# MCU.net
KiCad netlist of a schematic drawn in Altium Designer
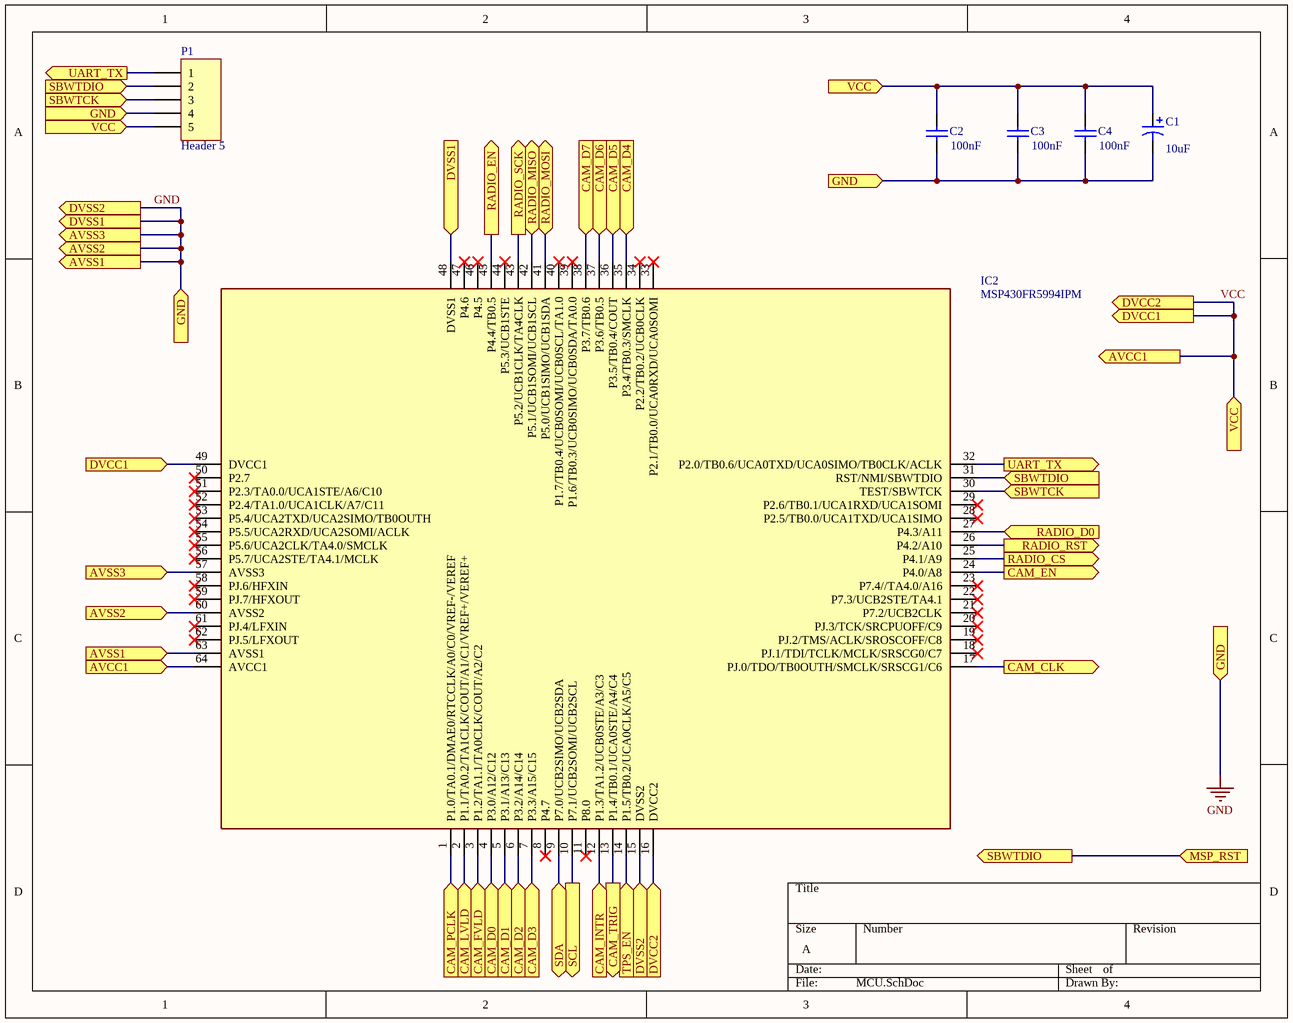
[diagram p0: MCU.SchDoc]

(export (version "E")
  (design (tool "Eeschema 10.0.6"))
  (components
    (comp (ref "C1")
      (value "10uF")
      (footprint "C1210")
      (description "Polarized Capacitor (Surface Mount)")
      (fields (field (name "PUBLISHER") "Altium Limited"))
      (libsource (lib "Miscellaneous Devices") (part "Cap Pol3"))
    )
    (comp (ref "C2")
      (value "100nF")
      (footprint "1608[0603]")
      (description "CAP CER 6.3V X5R/X7R 0603")
      (fields (field (name "Comment") "Cap") (field (name "PUBLISHER") "Altium Limited"))
      (libsource (lib "Miscellaneous Devices") (part "Cap"))
    )
    (comp (ref "C3")
      (value "100nF")
      (footprint "1608[0603]")
      (description "CAP CER 6.3V X5R/X7R 0603")
      (fields (field (name "Comment") "Cap") (field (name "PUBLISHER") "Altium Limited"))
      (libsource (lib "Miscellaneous Devices") (part "Cap"))
    )
    (comp (ref "C4")
      (value "100nF")
      (footprint "1608[0603]")
      (description "CAP CER 6.3V X5R/X7R 0603")
      (fields (field (name "Comment") "Cap") (field (name "PUBLISHER") "Altium Limited"))
      (libsource (lib "Miscellaneous Devices") (part "Cap"))
    )
    (comp (ref "IC2")
      (value "MSP430FR5994IPM")
      (footprint "SamacSys:QFP50P1200X1200X160-64N")
      (description "Integrated Circuit")
      (fields (field (name "MOUSER PART NUMBER") "595-MSP430FR5994IPM"))
      (libsource (lib "*") (part "MSP430FR5994IPM"))
    )
    (comp (ref "P1")
      (value "Header 5")
      (footprint "MHDR1X5")
      (description "Header, 5-Pin")
      (fields (field (name "PUBLISHER") "Altium Limited"))
      (libsource (lib "Miscellaneous Connectors") (part "Header 5"))
    )
  )
  (nets
    (net (code "1") (name "/CAM_CLK") (class "Default")
      (node (ref "IC2") (pin "17") (pinfunction "PJ.0/TDO/TB0OUTH/SMCLK/SRSCG1/C6_17") (pintype "passive"))
    )
    (net (code "2") (name "/CAM_D0") (class "Default")
      (node (ref "IC2") (pin "4") (pinfunction "P3.0/A12/C12_4") (pintype "passive"))
    )
    (net (code "3") (name "/CAM_D1") (class "Default")
      (node (ref "IC2") (pin "5") (pinfunction "P3.1/A13/C13_5") (pintype "passive"))
    )
    (net (code "4") (name "/CAM_D2") (class "Default")
      (node (ref "IC2") (pin "6") (pinfunction "P3.2/A14/C14_6") (pintype "passive"))
    )
    (net (code "5") (name "/CAM_D3") (class "Default")
      (node (ref "IC2") (pin "7") (pinfunction "P3.3/A15/C15_7") (pintype "passive"))
    )
    (net (code "6") (name "/CAM_D4") (class "Default")
      (node (ref "IC2") (pin "35") (pinfunction "P3.4/TB0.3/SMCLK_35") (pintype "passive"))
    )
    (net (code "7") (name "/CAM_D5") (class "Default")
      (node (ref "IC2") (pin "36") (pinfunction "P3.5/TB0.4/COUT_36") (pintype "passive"))
    )
    (net (code "8") (name "/CAM_D6") (class "Default")
      (node (ref "IC2") (pin "37") (pinfunction "P3.6/TB0.5_37") (pintype "passive"))
    )
    (net (code "9") (name "/CAM_D7") (class "Default")
      (node (ref "IC2") (pin "38") (pinfunction "P3.7/TB0.6_38") (pintype "passive"))
    )
    (net (code "10") (name "/CAM_EN") (class "Default")
      (node (ref "IC2") (pin "24") (pinfunction "P4.0/A8_24") (pintype "passive"))
    )
    (net (code "11") (name "/CAM_FVLD") (class "Default")
      (node (ref "IC2") (pin "3") (pinfunction "P1.2/TA1.1/TA0CLK/COUT/A2/C2_3") (pintype "passive"))
    )
    (net (code "12") (name "/CAM_INTR") (class "Default")
      (node (ref "IC2") (pin "12") (pinfunction "P1.3/TA1.2/UCB0STE/A3/C3_12") (pintype "passive"))
    )
    (net (code "13") (name "/CAM_LVLD") (class "Default")
      (node (ref "IC2") (pin "2") (pinfunction "P1.1/TA0.2/TA1CLK/COUT/A1/C1/VREF+/VEREF+_2") (pintype "passive"))
    )
    (net (code "14") (name "/CAM_PCLK") (class "Default")
      (node (ref "IC2") (pin "1") (pinfunction "P1.0/TA0.1/DMAE0/RTCCLK/A0/C0/VREF-/VEREF_1") (pintype "passive"))
    )
    (net (code "15") (name "/CAM_TRIG") (class "Default")
      (node (ref "IC2") (pin "13") (pinfunction "P1.4/TB0.1/UCA0STE/A4/C4_13") (pintype "passive"))
    )
    (net (code "16") (name "/MSP_RST") (class "Default")
      (node (ref "IC2") (pin "31") (pinfunction "RST/NMI/SBWTDIO_31") (pintype "passive"))
      (node (ref "P1") (pin "2") (pinfunction "2_2") (pintype "passive"))
    )
    (net (code "17") (name "/RADIO_CS") (class "Default")
      (node (ref "IC2") (pin "25") (pinfunction "P4.1/A9_25") (pintype "passive"))
    )
    (net (code "18") (name "/RADIO_D0") (class "Default")
      (node (ref "IC2") (pin "27") (pinfunction "P4.3/A11_27") (pintype "passive"))
    )
    (net (code "19") (name "/RADIO_EN") (class "Default")
      (node (ref "IC2") (pin "45") (pinfunction "P4.4/TB0.5_45") (pintype "passive"))
    )
    (net (code "20") (name "/RADIO_MISO") (class "Default")
      (node (ref "IC2") (pin "42") (pinfunction "P5.1/UCB1SOMI/UCB1SCL_42") (pintype "passive"))
    )
    (net (code "21") (name "/RADIO_MOSI") (class "Default")
      (node (ref "IC2") (pin "41") (pinfunction "P5.0/UCB1SIMO/UCB1SDA_41") (pintype "passive"))
    )
    (net (code "22") (name "/RADIO_RST") (class "Default")
      (node (ref "IC2") (pin "26") (pinfunction "P4.2/A10_26") (pintype "passive"))
    )
    (net (code "23") (name "/RADIO_SCK") (class "Default")
      (node (ref "IC2") (pin "43") (pinfunction "P5.2/UCB1CLK/TA4CLK_43") (pintype "passive"))
    )
    (net (code "24") (name "/SBWTCK") (class "Default")
      (node (ref "IC2") (pin "30") (pinfunction "TEST/SBWTCK_30") (pintype "passive"))
      (node (ref "P1") (pin "3") (pinfunction "3_3") (pintype "passive"))
    )
    (net (code "25") (name "/SCL") (class "Default")
      (node (ref "IC2") (pin "10") (pinfunction "P7.1/UCB2SOMI/UCB2SCL_10") (pintype "passive"))
    )
    (net (code "26") (name "/SDA") (class "Default")
      (node (ref "IC2") (pin "9") (pinfunction "P7.0/UCB2SIMO/UCB2SDA_9") (pintype "passive"))
    )
    (net (code "27") (name "/TPS_EN") (class "Default")
      (node (ref "IC2") (pin "14") (pinfunction "P1.5/TB0.2/UCA0CLK/A5/C5_14") (pintype "passive"))
    )
    (net (code "28") (name "/UART_TX") (class "Default")
      (node (ref "IC2") (pin "32") (pinfunction "P2.0/TB0.6/UCA0TXD/UCA0SIMO/TB0CLK/ACLK_32") (pintype "passive"))
      (node (ref "P1") (pin "1") (pinfunction "1_1") (pintype "passive"))
    )
    (net (code "29") (name "/VCC") (class "Default")
      (node (ref "C1") (pin "1") (pinfunction "1_1") (pintype "passive"))
      (node (ref "C2") (pin "2") (pinfunction "2_2") (pintype "passive"))
      (node (ref "C3") (pin "2") (pinfunction "2_2") (pintype "passive"))
      (node (ref "C4") (pin "2") (pinfunction "2_2") (pintype "passive"))
      (node (ref "IC2") (pin "16") (pinfunction "DVCC2_16") (pintype "passive"))
      (node (ref "IC2") (pin "49") (pinfunction "DVCC1_49") (pintype "passive"))
      (node (ref "IC2") (pin "64") (pinfunction "AVCC1_64") (pintype "passive"))
      (node (ref "P1") (pin "5") (pinfunction "5_5") (pintype "passive"))
    )
    (net (code "30") (name "GND") (class "Default")
      (node (ref "C1") (pin "2") (pinfunction "2_2") (pintype "passive"))
      (node (ref "C2") (pin "1") (pinfunction "1_1") (pintype "passive"))
      (node (ref "C3") (pin "1") (pinfunction "1_1") (pintype "passive"))
      (node (ref "C4") (pin "1") (pinfunction "1_1") (pintype "passive"))
      (node (ref "IC2") (pin "15") (pinfunction "DVSS2_15") (pintype "passive"))
      (node (ref "IC2") (pin "48") (pinfunction "DVSS1_48") (pintype "passive"))
      (node (ref "IC2") (pin "57") (pinfunction "AVSS3_57") (pintype "passive"))
      (node (ref "IC2") (pin "60") (pinfunction "AVSS2_60") (pintype "passive"))
      (node (ref "IC2") (pin "63") (pinfunction "AVSS1_63") (pintype "passive"))
      (node (ref "P1") (pin "4") (pinfunction "4_4") (pintype "passive"))
    )
    (net (code "31") (name "unconnected-(IC2-P1.6{slash}TB0.3{slash}UCB0SIMO{slash}UCB0SDA{slash}TA0.0-Pad39)") (class "Default")
      (node (ref "IC2") (pin "39") (pinfunction "P1.6/TB0.3/UCB0SIMO/UCB0SDA/TA0.0_39") (pintype "passive+no_connect"))
    )
    (net (code "32") (name "unconnected-(IC2-P1.7{slash}TB0.4{slash}UCB0SOMI{slash}UCB0SCL{slash}TA1.0-Pad40)") (class "Default")
      (node (ref "IC2") (pin "40") (pinfunction "P1.7/TB0.4/UCB0SOMI/UCB0SCL/TA1.0_40") (pintype "passive+no_connect"))
    )
    (net (code "33") (name "unconnected-(IC2-P2.1{slash}TB0.0{slash}UCA0RXD{slash}UCA0SOMI-Pad33)") (class "Default")
      (node (ref "IC2") (pin "33") (pinfunction "P2.1/TB0.0/UCA0RXD/UCA0SOMI_33") (pintype "passive+no_connect"))
    )
    (net (code "34") (name "unconnected-(IC2-P2.2{slash}TB0.2{slash}UCB0CLK-Pad34)") (class "Default")
      (node (ref "IC2") (pin "34") (pinfunction "P2.2/TB0.2/UCB0CLK_34") (pintype "passive+no_connect"))
    )
    (net (code "35") (name "unconnected-(IC2-P2.3{slash}TA0.0{slash}UCA1STE{slash}A6{slash}C10-Pad51)") (class "Default")
      (node (ref "IC2") (pin "51") (pinfunction "P2.3/TA0.0/UCA1STE/A6/C10_51") (pintype "passive+no_connect"))
    )
    (net (code "36") (name "unconnected-(IC2-P2.4{slash}TA1.0{slash}UCA1CLK{slash}A7{slash}C11-Pad52)") (class "Default")
      (node (ref "IC2") (pin "52") (pinfunction "P2.4/TA1.0/UCA1CLK/A7/C11_52") (pintype "passive+no_connect"))
    )
    (net (code "37") (name "unconnected-(IC2-P2.5{slash}TB0.0{slash}UCA1TXD{slash}UCA1SIMO-Pad28)") (class "Default")
      (node (ref "IC2") (pin "28") (pinfunction "P2.5/TB0.0/UCA1TXD/UCA1SIMO_28") (pintype "passive+no_connect"))
    )
    (net (code "38") (name "unconnected-(IC2-P2.6{slash}TB0.1{slash}UCA1RXD{slash}UCA1SOMI-Pad29)") (class "Default")
      (node (ref "IC2") (pin "29") (pinfunction "P2.6/TB0.1/UCA1RXD/UCA1SOMI_29") (pintype "passive+no_connect"))
    )
    (net (code "39") (name "unconnected-(IC2-P2.7-Pad50)") (class "Default")
      (node (ref "IC2") (pin "50") (pinfunction "P2.7_50") (pintype "passive+no_connect"))
    )
    (net (code "40") (name "unconnected-(IC2-P4.5-Pad46)") (class "Default")
      (node (ref "IC2") (pin "46") (pinfunction "P4.5_46") (pintype "passive+no_connect"))
    )
    (net (code "41") (name "unconnected-(IC2-P4.6-Pad47)") (class "Default")
      (node (ref "IC2") (pin "47") (pinfunction "P4.6_47") (pintype "passive+no_connect"))
    )
    (net (code "42") (name "unconnected-(IC2-P4.7-Pad8)") (class "Default")
      (node (ref "IC2") (pin "8") (pinfunction "P4.7_8") (pintype "passive+no_connect"))
    )
    (net (code "43") (name "unconnected-(IC2-P5.3{slash}UCB1STE-Pad44)") (class "Default")
      (node (ref "IC2") (pin "44") (pinfunction "P5.3/UCB1STE_44") (pintype "passive+no_connect"))
    )
    (net (code "44") (name "unconnected-(IC2-P5.4{slash}UCA2TXD{slash}UCA2SIMO{slash}TB0OUTH-Pad53)") (class "Default")
      (node (ref "IC2") (pin "53") (pinfunction "P5.4/UCA2TXD/UCA2SIMO/TB0OUTH_53") (pintype "passive+no_connect"))
    )
    (net (code "45") (name "unconnected-(IC2-P5.5{slash}UCA2RXD{slash}UCA2SOMI{slash}ACLK-Pad54)") (class "Default")
      (node (ref "IC2") (pin "54") (pinfunction "P5.5/UCA2RXD/UCA2SOMI/ACLK_54") (pintype "passive+no_connect"))
    )
    (net (code "46") (name "unconnected-(IC2-P5.6{slash}UCA2CLK{slash}TA4.0{slash}SMCLK-Pad55)") (class "Default")
      (node (ref "IC2") (pin "55") (pinfunction "P5.6/UCA2CLK/TA4.0/SMCLK_55") (pintype "passive+no_connect"))
    )
    (net (code "47") (name "unconnected-(IC2-P5.7{slash}UCA2STE{slash}TA4.1{slash}MCLK-Pad56)") (class "Default")
      (node (ref "IC2") (pin "56") (pinfunction "P5.7/UCA2STE/TA4.1/MCLK_56") (pintype "passive+no_connect"))
    )
    (net (code "48") (name "unconnected-(IC2-P7.2{slash}UCB2CLK-Pad21)") (class "Default")
      (node (ref "IC2") (pin "21") (pinfunction "P7.2/UCB2CLK_21") (pintype "passive+no_connect"))
    )
    (net (code "49") (name "unconnected-(IC2-P7.3{slash}UCB2STE{slash}TA4.1-Pad22)") (class "Default")
      (node (ref "IC2") (pin "22") (pinfunction "P7.3/UCB2STE/TA4.1_22") (pintype "passive+no_connect"))
    )
    (net (code "50") (name "unconnected-(IC2-P7.4{slash}{slash}TA4.0{slash}A16-Pad23)") (class "Default")
      (node (ref "IC2") (pin "23") (pinfunction "P7.4//TA4.0/A16_23") (pintype "passive+no_connect"))
    )
    (net (code "51") (name "unconnected-(IC2-P8.0-Pad11)") (class "Default")
      (node (ref "IC2") (pin "11") (pinfunction "P8.0_11") (pintype "passive+no_connect"))
    )
    (net (code "52") (name "unconnected-(IC2-PJ.1{slash}TDI{slash}TCLK{slash}MCLK{slash}SRSCG0{slash}C7-Pad18)") (class "Default")
      (node (ref "IC2") (pin "18") (pinfunction "PJ.1/TDI/TCLK/MCLK/SRSCG0/C7_18") (pintype "passive+no_connect"))
    )
    (net (code "53") (name "unconnected-(IC2-PJ.2{slash}TMS{slash}ACLK{slash}SROSCOFF{slash}C8-Pad19)") (class "Default")
      (node (ref "IC2") (pin "19") (pinfunction "PJ.2/TMS/ACLK/SROSCOFF/C8_19") (pintype "passive+no_connect"))
    )
    (net (code "54") (name "unconnected-(IC2-PJ.3{slash}TCK{slash}SRCPUOFF{slash}C9-Pad20)") (class "Default")
      (node (ref "IC2") (pin "20") (pinfunction "PJ.3/TCK/SRCPUOFF/C9_20") (pintype "passive+no_connect"))
    )
    (net (code "55") (name "unconnected-(IC2-PJ.4{slash}LFXIN-Pad61)") (class "Default")
      (node (ref "IC2") (pin "61") (pinfunction "PJ.4/LFXIN_61") (pintype "passive+no_connect"))
    )
    (net (code "56") (name "unconnected-(IC2-PJ.5{slash}LFXOUT-Pad62)") (class "Default")
      (node (ref "IC2") (pin "62") (pinfunction "PJ.5/LFXOUT_62") (pintype "passive+no_connect"))
    )
    (net (code "57") (name "unconnected-(IC2-PJ.6{slash}HFXIN-Pad58)") (class "Default")
      (node (ref "IC2") (pin "58") (pinfunction "PJ.6/HFXIN_58") (pintype "passive+no_connect"))
    )
    (net (code "58") (name "unconnected-(IC2-PJ.7{slash}HFXOUT-Pad59)") (class "Default")
      (node (ref "IC2") (pin "59") (pinfunction "PJ.7/HFXOUT_59") (pintype "passive+no_connect"))
    )
  )
)
